# bgm111-breakout.net
KiCad netlist of a schematic drawn in Altium Designer
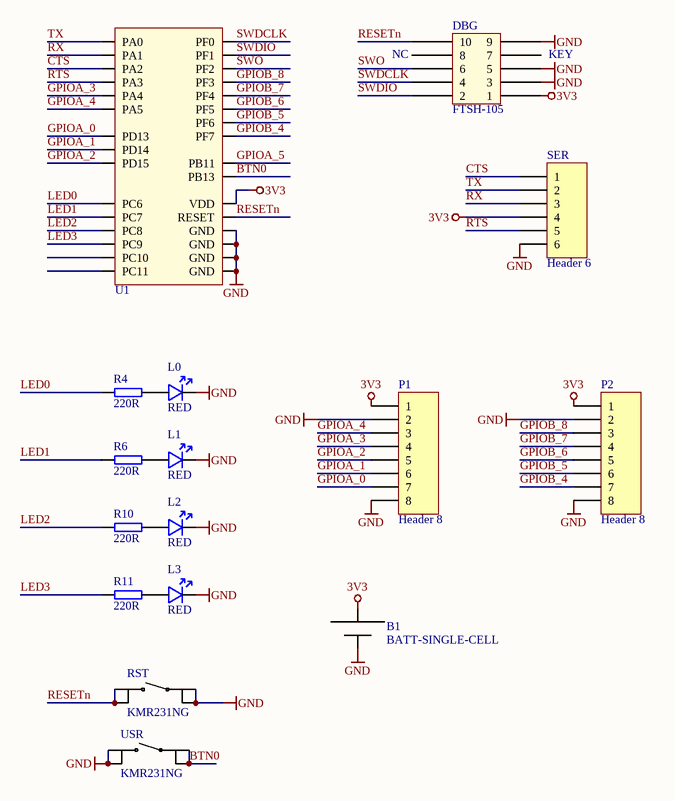
[diagram p0: bgm111-breakout.SchDoc]

(export (version "E")
  (design (tool "Eeschema 10.0.6"))
  (components
    (comp (ref "B1")
      (value "BATT-SINGLE-CELL")
      (footprint "3012")
      (description "BATT HOLDER COIN 16MM SMT")
      (fields (field (name "PART NUMBER") "3012") (field (name "MANUFACTURER") "Keystone"))
      (libsource (lib "electronpowered") (part "BATT-SINGLE-CELL"))
    )
    (comp (ref "DBG")
      (value "FTSH-105")
      (footprint "FTSH-105-XX-X-DV-K")
      (description "CONN HDR SM FTSH-105 10POS DUAL .05\"")
      (libsource (lib "electronpowered") (part "FTSH-105-01-X-DV-K"))
    )
    (comp (ref "L0")
      (value "RED")
      (footprint "SMT0603P")
      (description "LED SM 0603 RED 1V95 FWD VOLTAGE")
      (libsource (lib "electronpowered") (part "LNJ237W82RA"))
    )
    (comp (ref "L1")
      (value "RED")
      (footprint "SMT0603P")
      (description "LED SM 0603 RED 1V95 FWD VOLTAGE")
      (libsource (lib "electronpowered") (part "LNJ237W82RA"))
    )
    (comp (ref "L2")
      (value "RED")
      (footprint "SMT0603P")
      (description "LED SM 0603 RED 1V95 FWD VOLTAGE")
      (libsource (lib "electronpowered") (part "LNJ237W82RA"))
    )
    (comp (ref "L3")
      (value "RED")
      (footprint "SMT0603P")
      (description "LED SM 0603 RED 1V95 FWD VOLTAGE")
      (libsource (lib "electronpowered") (part "LNJ237W82RA"))
    )
    (comp (ref "P1")
      (value "Header 8")
      (footprint "HDR1X8")
      (description "Header, 8-Pin")
      (fields (field (name "PUBLISHER") "Altium Limited"))
      (libsource (lib "Miscellaneous Connectors") (part "Header 8"))
    )
    (comp (ref "P2")
      (value "Header 8")
      (footprint "HDR1X8")
      (description "Header, 8-Pin")
      (fields (field (name "PUBLISHER") "Altium Limited"))
      (libsource (lib "Miscellaneous Connectors") (part "Header 8"))
    )
    (comp (ref "R4")
      (value "220R")
      (footprint "SMT0603")
      (description "RES SM 0603 220R")
      (fields (field (name "Comment") "Resistor"))
      (libsource (lib "electronpowered") (part "RES-SM-0603-220R"))
    )
    (comp (ref "R6")
      (value "220R")
      (footprint "SMT0603")
      (description "RES SM 0603 220R")
      (fields (field (name "Comment") "Resistor"))
      (libsource (lib "electronpowered") (part "RES-SM-0603-220R"))
    )
    (comp (ref "R10")
      (value "220R")
      (footprint "SMT0603")
      (description "RES SM 0603 220R")
      (fields (field (name "Comment") "Resistor"))
      (libsource (lib "electronpowered") (part "RES-SM-0603-220R"))
    )
    (comp (ref "R11")
      (value "220R")
      (footprint "SMT0603")
      (description "RES SM 0603 220R")
      (fields (field (name "Comment") "Resistor"))
      (libsource (lib "electronpowered") (part "RES-SM-0603-220R"))
    )
    (comp (ref "RST")
      (value "KMR231NG")
      (footprint "KMR231NG")
      (description "PB SW SM TOP")
      (libsource (lib "electronpowered") (part "KMR231NG"))
    )
    (comp (ref "SER")
      (value "Header 6")
      (footprint "HDR1X6")
      (description "Header, 6-Pin")
      (fields (field (name "PUBLISHER") "Altium Limited"))
      (libsource (lib "Miscellaneous Connectors") (part "Header 6"))
    )
    (comp (ref "U1")
      (value "BGM111")
      (footprint "BGM111")
      (description "MODULE BLE BGM111")
      (libsource (lib "bgm111") (part "BGM111"))
    )
    (comp (ref "USR")
      (value "KMR231NG")
      (footprint "KMR231NG")
      (description "PB SW SM TOP")
      (libsource (lib "electronpowered") (part "KMR231NG"))
    )
  )
  (nets
    (net (code "1") (name "/BTN0") (class "Default")
      (node (ref "U1") (pin "13") (pinfunction "PB13_13") (pintype "passive"))
      (node (ref "USR") (pin "3") (pinfunction "3_3") (pintype "passive"))
      (node (ref "USR") (pin "4") (pinfunction "4_4") (pintype "passive"))
    )
    (net (code "2") (name "/CTS") (class "Default")
      (node (ref "SER") (pin "1") (pinfunction "1_1") (pintype "passive"))
      (node (ref "U1") (pin "7") (pinfunction "PA2_7") (pintype "passive"))
    )
    (net (code "3") (name "/GPIOA_0") (class "Default")
      (node (ref "P1") (pin "7") (pinfunction "7_7") (pintype "passive"))
      (node (ref "U1") (pin "2") (pinfunction "PD13_2") (pintype "passive"))
    )
    (net (code "4") (name "/GPIOA_1") (class "Default")
      (node (ref "P1") (pin "6") (pinfunction "6_6") (pintype "passive"))
      (node (ref "U1") (pin "3") (pinfunction "PD14_3") (pintype "passive"))
    )
    (net (code "5") (name "/GPIOA_2") (class "Default")
      (node (ref "P1") (pin "5") (pinfunction "5_5") (pintype "passive"))
      (node (ref "U1") (pin "4") (pinfunction "PD15_4") (pintype "passive"))
    )
    (net (code "6") (name "/GPIOA_3") (class "Default")
      (node (ref "P1") (pin "4") (pinfunction "4_4") (pintype "passive"))
      (node (ref "U1") (pin "9") (pinfunction "PA4_9") (pintype "passive"))
    )
    (net (code "7") (name "/GPIOA_4") (class "Default")
      (node (ref "P1") (pin "3") (pinfunction "3_3") (pintype "passive"))
      (node (ref "U1") (pin "10") (pinfunction "PA5_10") (pintype "passive"))
    )
    (net (code "8") (name "/GPIOA_5") (class "Default")
      (node (ref "U1") (pin "11") (pinfunction "PB11_11") (pintype "passive"))
    )
    (net (code "9") (name "/GPIOB_4") (class "Default")
      (node (ref "P2") (pin "7") (pinfunction "7_7") (pintype "passive"))
      (node (ref "U1") (pin "28") (pinfunction "PF7_28") (pintype "passive"))
    )
    (net (code "10") (name "/GPIOB_5") (class "Default")
      (node (ref "P2") (pin "6") (pinfunction "6_6") (pintype "passive"))
      (node (ref "U1") (pin "27") (pinfunction "PF6_27") (pintype "passive"))
    )
    (net (code "11") (name "/GPIOB_6") (class "Default")
      (node (ref "P2") (pin "5") (pinfunction "5_5") (pintype "passive"))
      (node (ref "U1") (pin "26") (pinfunction "PF5_26") (pintype "passive"))
    )
    (net (code "12") (name "/GPIOB_7") (class "Default")
      (node (ref "P2") (pin "4") (pinfunction "4_4") (pintype "passive"))
      (node (ref "U1") (pin "25") (pinfunction "PF4_25") (pintype "passive"))
    )
    (net (code "13") (name "/GPIOB_8") (class "Default")
      (node (ref "P2") (pin "3") (pinfunction "3_3") (pintype "passive"))
      (node (ref "U1") (pin "24") (pinfunction "PF3_24") (pintype "passive"))
    )
    (net (code "14") (name "/LED0") (class "Default")
      (node (ref "R4") (pin "2") (pinfunction "2_2") (pintype "passive"))
      (node (ref "U1") (pin "14") (pinfunction "PC6_14") (pintype "passive"))
    )
    (net (code "15") (name "/LED1") (class "Default")
      (node (ref "R6") (pin "2") (pinfunction "2_2") (pintype "passive"))
      (node (ref "U1") (pin "15") (pinfunction "PC7_15") (pintype "passive"))
    )
    (net (code "16") (name "/LED2") (class "Default")
      (node (ref "R10") (pin "2") (pinfunction "2_2") (pintype "passive"))
      (node (ref "U1") (pin "16") (pinfunction "PC8_16") (pintype "passive"))
    )
    (net (code "17") (name "/LED3") (class "Default")
      (node (ref "R11") (pin "2") (pinfunction "2_2") (pintype "passive"))
      (node (ref "U1") (pin "17") (pinfunction "PC9_17") (pintype "passive"))
    )
    (net (code "18") (name "/RESETn") (class "Default")
      (node (ref "DBG") (pin "10") (pinfunction "10_10") (pintype "passive"))
      (node (ref "RST") (pin "1") (pinfunction "1_1") (pintype "passive"))
      (node (ref "RST") (pin "2") (pinfunction "2_2") (pintype "passive"))
      (node (ref "U1") (pin "30") (pinfunction "RESET_30") (pintype "passive"))
    )
    (net (code "19") (name "/RTS") (class "Default")
      (node (ref "SER") (pin "5") (pinfunction "5_5") (pintype "passive"))
      (node (ref "U1") (pin "8") (pinfunction "PA3_8") (pintype "passive"))
    )
    (net (code "20") (name "/RX") (class "Default")
      (node (ref "SER") (pin "3") (pinfunction "3_3") (pintype "passive"))
      (node (ref "U1") (pin "6") (pinfunction "PA1_6") (pintype "passive"))
    )
    (net (code "21") (name "/SWDCLK") (class "Default")
      (node (ref "DBG") (pin "4") (pinfunction "4_4") (pintype "passive"))
      (node (ref "U1") (pin "21") (pinfunction "PF0_21") (pintype "passive"))
    )
    (net (code "22") (name "/SWDIO") (class "Default")
      (node (ref "DBG") (pin "2") (pinfunction "2_2") (pintype "passive"))
      (node (ref "U1") (pin "22") (pinfunction "PF1_22") (pintype "passive"))
    )
    (net (code "23") (name "/SWO") (class "Default")
      (node (ref "DBG") (pin "6") (pinfunction "6_6") (pintype "passive"))
      (node (ref "U1") (pin "23") (pinfunction "PF2_23") (pintype "passive"))
    )
    (net (code "24") (name "/TX") (class "Default")
      (node (ref "SER") (pin "2") (pinfunction "2_2") (pintype "passive"))
      (node (ref "U1") (pin "5") (pinfunction "PA0_5") (pintype "passive"))
    )
    (net (code "25") (name "3V3") (class "Default")
      (node (ref "B1") (pin "1") (pinfunction "+_1") (pintype "passive"))
      (node (ref "DBG") (pin "1") (pinfunction "1_1") (pintype "passive"))
      (node (ref "P1") (pin "1") (pinfunction "1_1") (pintype "passive"))
      (node (ref "P2") (pin "1") (pinfunction "1_1") (pintype "passive"))
      (node (ref "SER") (pin "4") (pinfunction "4_4") (pintype "passive"))
      (node (ref "U1") (pin "29") (pinfunction "VDD_29") (pintype "passive"))
    )
    (net (code "26") (name "GND") (class "Default")
      (node (ref "B1") (pin "0") (pinfunction "-_0") (pintype "passive"))
      (node (ref "DBG") (pin "3") (pinfunction "3_3") (pintype "passive"))
      (node (ref "DBG") (pin "5") (pinfunction "5_5") (pintype "passive"))
      (node (ref "DBG") (pin "9") (pinfunction "9_9") (pintype "passive"))
      (node (ref "L0") (pin "2") (pinfunction "2_2") (pintype "passive"))
      (node (ref "L1") (pin "2") (pinfunction "2_2") (pintype "passive"))
      (node (ref "L2") (pin "2") (pinfunction "2_2") (pintype "passive"))
      (node (ref "L3") (pin "2") (pinfunction "2_2") (pintype "passive"))
      (node (ref "P1") (pin "2") (pinfunction "2_2") (pintype "passive"))
      (node (ref "P1") (pin "8") (pinfunction "8_8") (pintype "passive"))
      (node (ref "P2") (pin "2") (pinfunction "2_2") (pintype "passive"))
      (node (ref "P2") (pin "8") (pinfunction "8_8") (pintype "passive"))
      (node (ref "RST") (pin "3") (pinfunction "3_3") (pintype "passive"))
      (node (ref "RST") (pin "4") (pinfunction "4_4") (pintype "passive"))
      (node (ref "SER") (pin "6") (pinfunction "6_6") (pintype "passive"))
      (node (ref "U1") (pin "1") (pinfunction "GND_1") (pintype "passive"))
      (node (ref "U1") (pin "12") (pinfunction "GND_12") (pintype "passive"))
      (node (ref "U1") (pin "20") (pinfunction "GND_20") (pintype "passive"))
      (node (ref "U1") (pin "31") (pinfunction "GND_31") (pintype "passive"))
      (node (ref "USR") (pin "1") (pinfunction "1_1") (pintype "passive"))
      (node (ref "USR") (pin "2") (pinfunction "2_2") (pintype "passive"))
    )
    (net (code "27") (name "Net-(L0-Pad1)") (class "Default")
      (node (ref "L0") (pin "1") (pinfunction "1_1") (pintype "passive"))
      (node (ref "R4") (pin "1") (pinfunction "1_1") (pintype "passive"))
    )
    (net (code "28") (name "Net-(L1-Pad1)") (class "Default")
      (node (ref "L1") (pin "1") (pinfunction "1_1") (pintype "passive"))
      (node (ref "R6") (pin "1") (pinfunction "1_1") (pintype "passive"))
    )
    (net (code "29") (name "Net-(L2-Pad1)") (class "Default")
      (node (ref "L2") (pin "1") (pinfunction "1_1") (pintype "passive"))
      (node (ref "R10") (pin "1") (pinfunction "1_1") (pintype "passive"))
    )
    (net (code "30") (name "Net-(L3-Pad1)") (class "Default")
      (node (ref "L3") (pin "1") (pinfunction "1_1") (pintype "passive"))
      (node (ref "R11") (pin "1") (pinfunction "1_1") (pintype "passive"))
    )
    (net (code "31") (name "unconnected-(DBG-Pad7)") (class "Default")
      (node (ref "DBG") (pin "7") (pinfunction "7_7") (pintype "passive"))
    )
    (net (code "32") (name "unconnected-(DBG-Pad8)") (class "Default")
      (node (ref "DBG") (pin "8") (pinfunction "8_8") (pintype "passive"))
    )
    (net (code "33") (name "unconnected-(U1-PC10-Pad18)") (class "Default")
      (node (ref "U1") (pin "18") (pinfunction "PC10_18") (pintype "passive"))
    )
    (net (code "34") (name "unconnected-(U1-PC11-Pad19)") (class "Default")
      (node (ref "U1") (pin "19") (pinfunction "PC11_19") (pintype "passive"))
    )
  )
)
